# 07_-CPU-ENET_GPIO.net
KiCad netlist of a schematic drawn in Altium Designer
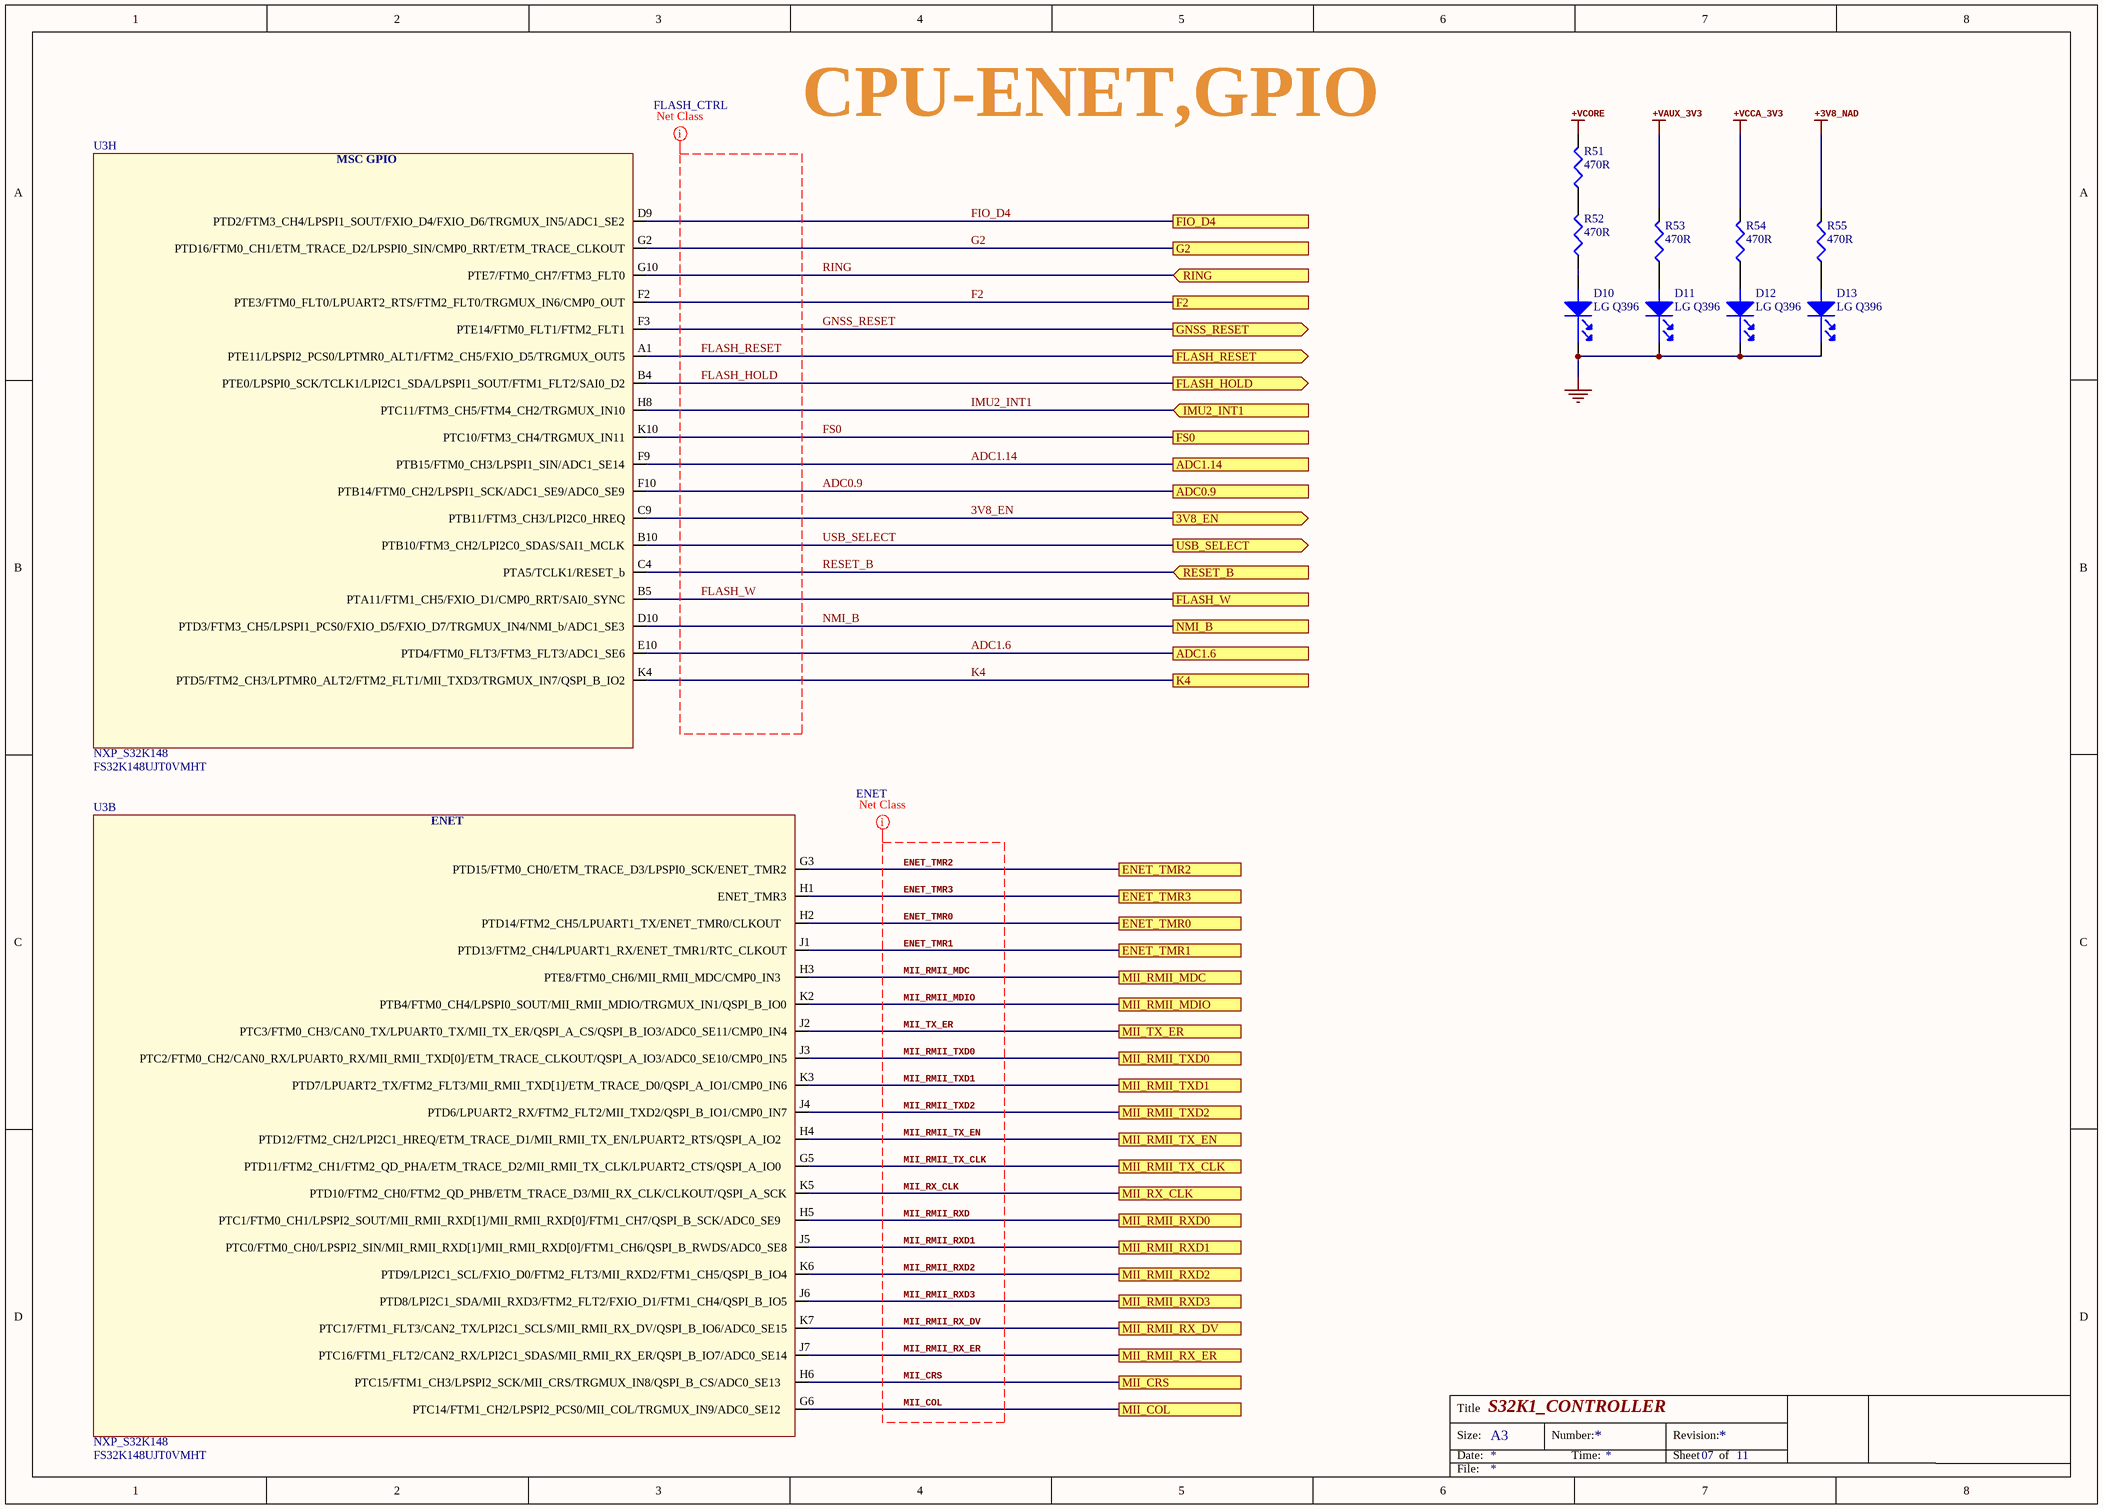
[diagram p0: [07]-CPU-ENET,GPIO.SchDoc]

(export (version "E")
  (design (tool "Eeschema 10.0.6"))
  (components
    (comp (ref "D10")
      (value "LG Q396")
      (footprint "LED_0603")
      (description "Green Led Chipled 0603 Lg Q396")
      (fields (field (name "MANUFACTURER") "Osram Opto"))
      (libsource (lib "altium-import") (part "root_3_LG Q396_"))
    )
    (comp (ref "D11")
      (value "LG Q396")
      (footprint "LED_0603")
      (description "Green Led Chipled 0603 Lg Q396")
      (fields (field (name "MANUFACTURER") "Osram Opto"))
      (libsource (lib "altium-import") (part "root_3_LG Q396_"))
    )
    (comp (ref "D12")
      (value "LG Q396")
      (footprint "LED_0603")
      (description "Green Led Chipled 0603 Lg Q396")
      (fields (field (name "MANUFACTURER") "Osram Opto"))
      (libsource (lib "altium-import") (part "root_3_LG Q396_"))
    )
    (comp (ref "D13")
      (value "LG Q396")
      (footprint "LED_0603")
      (description "Green Led Chipled 0603 Lg Q396")
      (fields (field (name "MANUFACTURER") "Osram Opto"))
      (libsource (lib "altium-import") (part "root_3_LG Q396_"))
    )
    (comp (ref "R51")
      (value "AC0402JR-07470RL")
      (footprint "RES0402")
      (description "Res Thick Film 0402 470 Ohm 5% 0.063W(1/16W) ±100ppm/C Epoxy Pad SMD Automotive T/R")
      (fields
        (field (name "MANUFACTURER") "Yageo")
        (field (name "TOLERANCE") "5%")
        (field (name "RESISTANCE") "470R")
      )
      (libsource (lib "altium-import") (part "root_1_AC0402JR-07470RL_"))
    )
    (comp (ref "R52")
      (value "AC0402JR-07470RL")
      (footprint "RES0402")
      (description "Res Thick Film 0402 470 Ohm 5% 0.063W(1/16W) ±100ppm/C Epoxy Pad SMD Automotive T/R")
      (fields
        (field (name "MANUFACTURER") "Yageo")
        (field (name "TOLERANCE") "5%")
        (field (name "RESISTANCE") "470R")
      )
      (libsource (lib "altium-import") (part "root_1_AC0402JR-07470RL_"))
    )
    (comp (ref "R53")
      (value "AC0402JR-07470RL")
      (footprint "RES0402")
      (description "Res Thick Film 0402 470 Ohm 5% 0.063W(1/16W) ±100ppm/C Epoxy Pad SMD Automotive T/R")
      (fields
        (field (name "MANUFACTURER") "Yageo")
        (field (name "TOLERANCE") "5%")
        (field (name "RESISTANCE") "470R")
      )
      (libsource (lib "altium-import") (part "root_1_AC0402JR-07470RL_"))
    )
    (comp (ref "R54")
      (value "AC0402JR-07470RL")
      (footprint "RES0402")
      (description "Res Thick Film 0402 470 Ohm 5% 0.063W(1/16W) ±100ppm/C Epoxy Pad SMD Automotive T/R")
      (fields
        (field (name "MANUFACTURER") "Yageo")
        (field (name "TOLERANCE") "5%")
        (field (name "RESISTANCE") "470R")
      )
      (libsource (lib "altium-import") (part "root_1_AC0402JR-07470RL_"))
    )
    (comp (ref "R55")
      (value "AC0402JR-07470RL")
      (footprint "RES0402")
      (description "Res Thick Film 0402 470 Ohm 5% 0.063W(1/16W) ±100ppm/C Epoxy Pad SMD Automotive T/R")
      (fields
        (field (name "MANUFACTURER") "Yageo")
        (field (name "TOLERANCE") "5%")
        (field (name "RESISTANCE") "470R")
      )
      (libsource (lib "altium-import") (part "root_1_AC0402JR-07470RL_"))
    )
    (comp (ref "U3")
      (value "NXP_S32K148")
      (footprint "WEONREFERENCEPLATFORM_100MAPBGA")
      (fields
        (field (name "MANUFACTURER") "NXP Semiconductors")
        (field (name "MANUFACTURER PART NUMBER") "FS32K148UJT0VMHT")
      )
      (libsource (lib "WeOnReferenceBoard") (part "NXP_S32K148"))
    )
  )
  (nets
    (net (code "1") (name "+3V8_NAD") (class "Default")
      (node (ref "R55") (pin "2") (pinfunction "2_2") (pintype "passive"))
    )
    (net (code "2") (name "+VAUX_3V3") (class "Default")
      (node (ref "R53") (pin "2") (pinfunction "2_2") (pintype "passive"))
    )
    (net (code "3") (name "+VCCA_3V3") (class "Default")
      (node (ref "R54") (pin "2") (pinfunction "2_2") (pintype "passive"))
    )
    (net (code "4") (name "+VCORE") (class "Default")
      (node (ref "R51") (pin "2") (pinfunction "2_2") (pintype "passive"))
    )
    (net (code "5") (name "/3V8_EN") (class "Default")
      (node (ref "U3") (pin "C9") (pinfunction "PTB11/FTM3_CH3/LPI2C0_HREQ_C9") (pintype "passive"))
    )
    (net (code "6") (name "/ADC0.9") (class "Default")
      (node (ref "U3") (pin "F10") (pinfunction "PTB14/FTM0_CH2/LPSPI1_SCK/ADC1_SE9/ADC0_SE9_F10") (pintype "passive"))
    )
    (net (code "7") (name "/ADC1.6") (class "Default")
      (node (ref "U3") (pin "E10") (pinfunction "PTD4/FTM0_FLT3/FTM3_FLT3/ADC1_SE6_E10") (pintype "passive"))
    )
    (net (code "8") (name "/ADC1.14") (class "Default")
      (node (ref "U3") (pin "F9") (pinfunction "PTB15/FTM0_CH3/LPSPI1_SIN/ADC1_SE14_F9") (pintype "passive"))
    )
    (net (code "9") (name "/ENET_TMR0") (class "Default")
      (node (ref "U3") (pin "H2") (pinfunction "PTD14/FTM2_CH5/LPUART1_TX/ENET_TMR0/CLKOUT_H2") (pintype "passive"))
    )
    (net (code "10") (name "/ENET_TMR1") (class "Default")
      (node (ref "U3") (pin "J1") (pinfunction "PTD13/FTM2_CH4/LPUART1_RX/ENET_TMR1/RTC_CLKOUT_J1") (pintype "passive"))
    )
    (net (code "11") (name "/ENET_TMR2") (class "Default")
      (node (ref "U3") (pin "G3") (pinfunction "PTD15/FTM0_CH0/ETM_TRACE_D3/LPSPI0_SCK/ENET_TMR2_G3") (pintype "passive"))
    )
    (net (code "12") (name "/ENET_TMR3") (class "Default")
      (node (ref "U3") (pin "H1") (pinfunction "ENET_TMR3_H1") (pintype "passive"))
    )
    (net (code "13") (name "/F2") (class "Default")
      (node (ref "U3") (pin "F2") (pinfunction "PTE3/FTM0_FLT0/LPUART2_RTS/FTM2_FLT0/TRGMUX_IN6/CMP0_OUT_F2") (pintype "passive"))
    )
    (net (code "14") (name "/FIO_D4") (class "Default")
      (node (ref "U3") (pin "D9") (pinfunction "PTD2/FTM3_CH4/LPSPI1_SOUT/FXIO_D4/FXIO_D6/TRGMUX_IN5/ADC1_SE2_D9") (pintype "passive"))
    )
    (net (code "15") (name "/FLASH_HOLD") (class "Default")
      (node (ref "U3") (pin "B4") (pinfunction "PTE0/LPSPI0_SCK/TCLK1/LPI2C1_SDA/LPSPI1_SOUT/FTM1_FLT2/SAI0_D2_B4") (pintype "passive"))
    )
    (net (code "16") (name "/FLASH_RESET") (class "Default")
      (node (ref "U3") (pin "A1") (pinfunction "PTE11/LPSPI2_PCS0/LPTMR0_ALT1/FTM2_CH5/FXIO_D5/TRGMUX_OUT5_A1") (pintype "passive"))
    )
    (net (code "17") (name "/FLASH_W") (class "Default")
      (node (ref "U3") (pin "B5") (pinfunction "PTA11/FTM1_CH5/FXIO_D1/CMP0_RRT/SAI0_SYNC_B5") (pintype "passive"))
    )
    (net (code "18") (name "/FS0") (class "Default")
      (node (ref "U3") (pin "K10") (pinfunction "PTC10/FTM3_CH4/TRGMUX_IN11_K10") (pintype "passive"))
    )
    (net (code "19") (name "/G2") (class "Default")
      (node (ref "U3") (pin "G2") (pinfunction "PTD16/FTM0_CH1/ETM_TRACE_D2/LPSPI0_SIN/CMP0_RRT/ETM_TRACE_CLKOUT_G2") (pintype "passive"))
    )
    (net (code "20") (name "/GNSS_RESET") (class "Default")
      (node (ref "U3") (pin "F3") (pinfunction "PTE14/FTM0_FLT1/FTM2_FLT1_F3") (pintype "passive"))
    )
    (net (code "21") (name "/IMU2_INT1") (class "Default")
      (node (ref "U3") (pin "H8") (pinfunction "PTC11/FTM3_CH5/FTM4_CH2/TRGMUX_IN10_H8") (pintype "passive"))
    )
    (net (code "22") (name "/K4") (class "Default")
      (node (ref "U3") (pin "K4") (pinfunction "PTD5/FTM2_CH3/LPTMR0_ALT2/FTM2_FLT1/MII_TXD3/TRGMUX_IN7/QSPI_B_IO2_K4") (pintype "passive"))
    )
    (net (code "23") (name "/MII_COL") (class "Default")
      (node (ref "U3") (pin "G6") (pinfunction "PTC14/FTM1_CH2/LPSPI2_PCS0/MII_COL/TRGMUX_IN9/ADC0_SE12_G6") (pintype "passive"))
    )
    (net (code "24") (name "/MII_CRS") (class "Default")
      (node (ref "U3") (pin "H6") (pinfunction "PTC15/FTM1_CH3/LPSPI2_SCK/MII_CRS/TRGMUX_IN8/QSPI_B_CS/ADC0_SE13_H6") (pintype "passive"))
    )
    (net (code "25") (name "/MII_RMII_MDC") (class "Default")
      (node (ref "U3") (pin "H3") (pinfunction "PTE8/FTM0_CH6/MII_RMII_MDC/CMP0_IN3_H3") (pintype "passive"))
    )
    (net (code "26") (name "/MII_RMII_MDIO") (class "Default")
      (node (ref "U3") (pin "K2") (pinfunction "PTB4/FTM0_CH4/LPSPI0_SOUT/MII_RMII_MDIO/TRGMUX_IN1/QSPI_B_IO0_K2") (pintype "passive"))
    )
    (net (code "27") (name "/MII_RMII_RXD") (class "Default")
      (node (ref "U3") (pin "H5") (pinfunction "PTC1/FTM0_CH1/LPSPI2_SOUT/MII_RMII_RXD[1]/MII_RMII_RXD[0]/FTM1_CH7/QSPI_B_SCK/ADC0_SE9_H5") (pintype "passive"))
    )
    (net (code "28") (name "/MII_RMII_RXD1") (class "Default")
      (node (ref "U3") (pin "J5") (pinfunction "PTC0/FTM0_CH0/LPSPI2_SIN/MII_RMII_RXD[1]/MII_RMII_RXD[0]/FTM1_CH6/QSPI_B_RWDS/ADC0_SE8_J5") (pintype "passive"))
    )
    (net (code "29") (name "/MII_RMII_RXD2") (class "Default")
      (node (ref "U3") (pin "K6") (pinfunction "PTD9/LPI2C1_SCL/FXIO_D0/FTM2_FLT3/MII_RXD2/FTM1_CH5/QSPI_B_IO4_K6") (pintype "passive"))
    )
    (net (code "30") (name "/MII_RMII_RXD3") (class "Default")
      (node (ref "U3") (pin "J6") (pinfunction "PTD8/LPI2C1_SDA/MII_RXD3/FTM2_FLT2/FXIO_D1/FTM1_CH4/QSPI_B_IO5_J6") (pintype "passive"))
    )
    (net (code "31") (name "/MII_RMII_RX_DV") (class "Default")
      (node (ref "U3") (pin "K7") (pinfunction "PTC17/FTM1_FLT3/CAN2_TX/LPI2C1_SCLS/MII_RMII_RX_DV/QSPI_B_IO6/ADC0_SE15_K7") (pintype "passive"))
    )
    (net (code "32") (name "/MII_RMII_RX_ER") (class "Default")
      (node (ref "U3") (pin "J7") (pinfunction "PTC16/FTM1_FLT2/CAN2_RX/LPI2C1_SDAS/MII_RMII_RX_ER/QSPI_B_IO7/ADC0_SE14_J7") (pintype "passive"))
    )
    (net (code "33") (name "/MII_RMII_TXD0") (class "Default")
      (node (ref "U3") (pin "J3") (pinfunction "PTC2/FTM0_CH2/CAN0_RX/LPUART0_RX/MII_RMII_TXD[0]/ETM_TRACE_CLKOUT/QSPI_A_IO3/ADC0_SE10/CMP0_IN5_J3") (pintype "passive"))
    )
    (net (code "34") (name "/MII_RMII_TXD1") (class "Default")
      (node (ref "U3") (pin "K3") (pinfunction "PTD7/LPUART2_TX/FTM2_FLT3/MII_RMII_TXD[1]/ETM_TRACE_D0/QSPI_A_IO1/CMP0_IN6_K3") (pintype "passive"))
    )
    (net (code "35") (name "/MII_RMII_TXD2") (class "Default")
      (node (ref "U3") (pin "J4") (pinfunction "PTD6/LPUART2_RX/FTM2_FLT2/MII_TXD2/QSPI_B_IO1/CMP0_IN7_J4") (pintype "passive"))
    )
    (net (code "36") (name "/MII_RMII_TX_CLK") (class "Default")
      (node (ref "U3") (pin "G5") (pinfunction "PTD11/FTM2_CH1/FTM2_QD_PHA/ETM_TRACE_D2/MII_RMII_TX_CLK/LPUART2_CTS/QSPI_A_IO0_G5") (pintype "passive"))
    )
    (net (code "37") (name "/MII_RMII_TX_EN") (class "Default")
      (node (ref "U3") (pin "H4") (pinfunction "PTD12/FTM2_CH2/LPI2C1_HREQ/ETM_TRACE_D1/MII_RMII_TX_EN/LPUART2_RTS/QSPI_A_IO2_H4") (pintype "passive"))
    )
    (net (code "38") (name "/MII_RX_CLK") (class "Default")
      (node (ref "U3") (pin "K5") (pinfunction "PTD10/FTM2_CH0/FTM2_QD_PHB/ETM_TRACE_D3/MII_RX_CLK/CLKOUT/QSPI_A_SCK_K5") (pintype "passive"))
    )
    (net (code "39") (name "/MII_TX_ER") (class "Default")
      (node (ref "U3") (pin "J2") (pinfunction "PTC3/FTM0_CH3/CAN0_TX/LPUART0_TX/MII_TX_ER/QSPI_A_CS/QSPI_B_IO3/ADC0_SE11/CMP0_IN4_J2") (pintype "passive"))
    )
    (net (code "40") (name "/NMI_B") (class "Default")
      (node (ref "U3") (pin "D10") (pinfunction "PTD3/FTM3_CH5/LPSPI1_PCS0/FXIO_D5/FXIO_D7/TRGMUX_IN4/NMI_b/ADC1_SE3_D10") (pintype "passive"))
    )
    (net (code "41") (name "/RESET_B") (class "Default")
      (node (ref "U3") (pin "C4") (pinfunction "PTA5/TCLK1/RESET_b_C4") (pintype "passive"))
    )
    (net (code "42") (name "/RING") (class "Default")
      (node (ref "U3") (pin "G10") (pinfunction "PTE7/FTM0_CH7/FTM3_FLT0_G10") (pintype "passive"))
    )
    (net (code "43") (name "/USB_SELECT") (class "Default")
      (node (ref "U3") (pin "B10") (pinfunction "PTB10/FTM3_CH2/LPI2C0_SDAS/SAI1_MCLK_B10") (pintype "passive"))
    )
    (net (code "44") (name "GND") (class "Default")
      (node (ref "D10") (pin "1") (pinfunction "cathode_1") (pintype "passive"))
      (node (ref "D11") (pin "1") (pinfunction "cathode_1") (pintype "passive"))
      (node (ref "D12") (pin "1") (pinfunction "cathode_1") (pintype "passive"))
      (node (ref "D13") (pin "1") (pinfunction "cathode_1") (pintype "passive"))
    )
    (net (code "45") (name "Net-(D10-ANODE)") (class "Default")
      (node (ref "D10") (pin "2") (pinfunction "ANODE_2") (pintype "passive"))
      (node (ref "R52") (pin "1") (pinfunction "1_1") (pintype "passive"))
    )
    (net (code "46") (name "Net-(D11-ANODE)") (class "Default")
      (node (ref "D11") (pin "2") (pinfunction "ANODE_2") (pintype "passive"))
      (node (ref "R53") (pin "1") (pinfunction "1_1") (pintype "passive"))
    )
    (net (code "47") (name "Net-(D12-ANODE)") (class "Default")
      (node (ref "D12") (pin "2") (pinfunction "ANODE_2") (pintype "passive"))
      (node (ref "R54") (pin "1") (pinfunction "1_1") (pintype "passive"))
    )
    (net (code "48") (name "Net-(D13-ANODE)") (class "Default")
      (node (ref "D13") (pin "2") (pinfunction "ANODE_2") (pintype "passive"))
      (node (ref "R55") (pin "1") (pinfunction "1_1") (pintype "passive"))
    )
    (net (code "49") (name "Net-(R51-Pad1)") (class "Default")
      (node (ref "R51") (pin "1") (pinfunction "1_1") (pintype "passive"))
      (node (ref "R52") (pin "2") (pinfunction "2_2") (pintype "passive"))
    )
  )
)
